# USB.net
KiCad netlist of a schematic drawn in Altium Designer
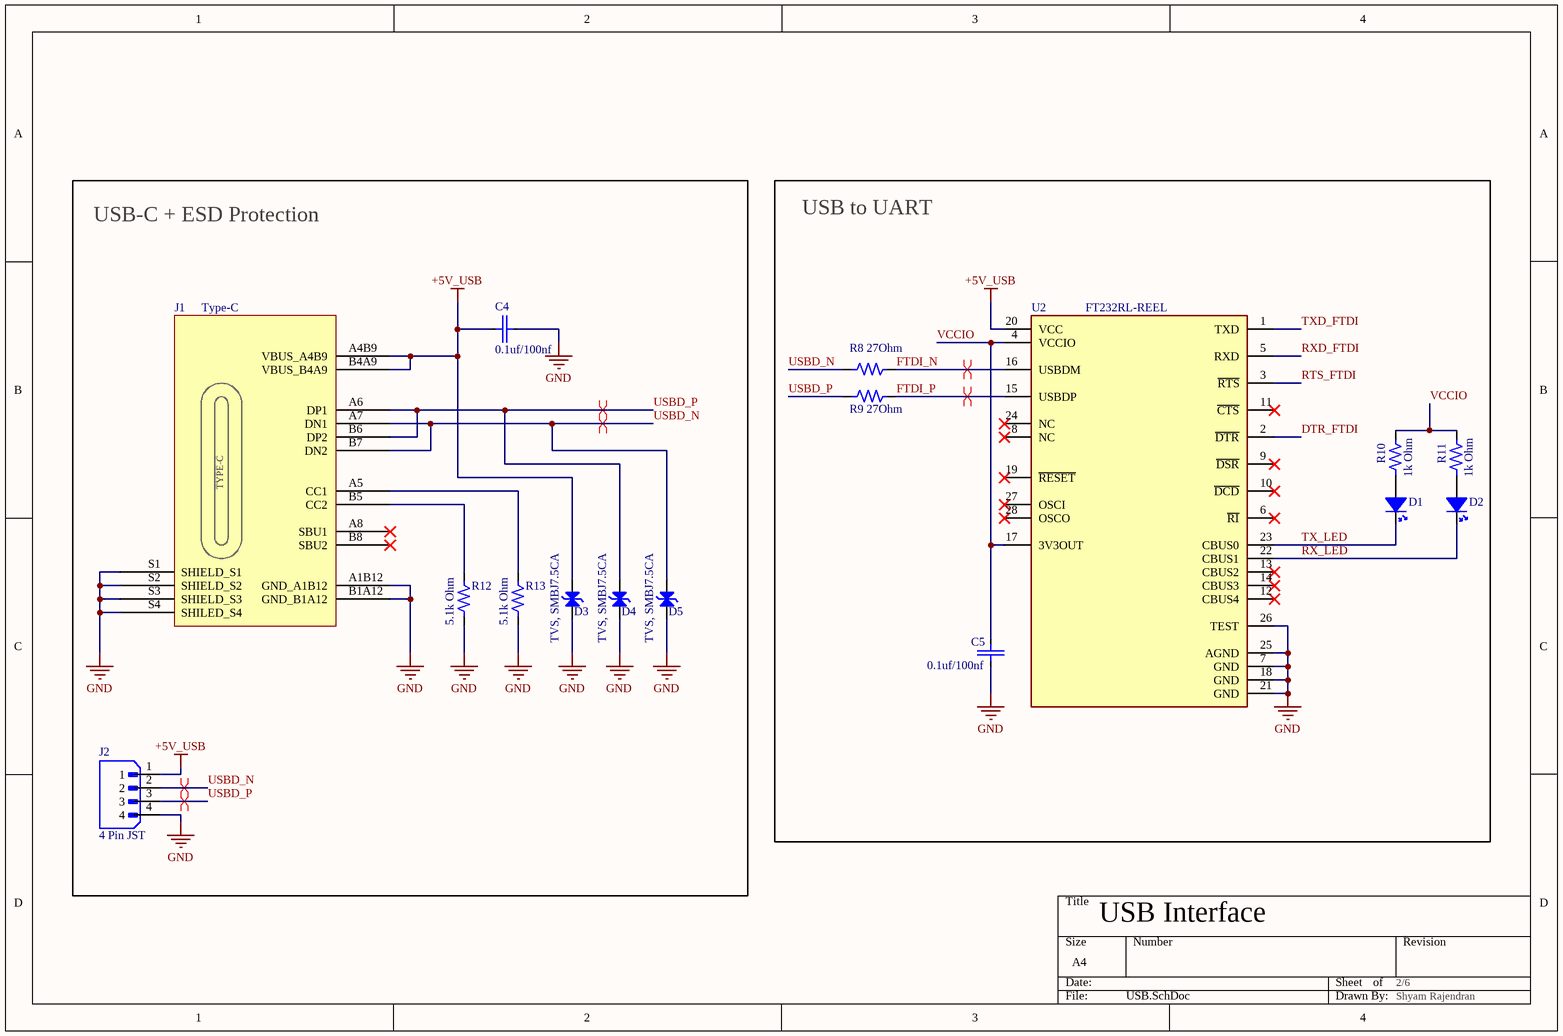
[diagram p0: USB.SchDoc]

(export (version "E")
  (design (tool "Eeschema 10.0.6"))
  (components
    (comp (ref "C4")
      (value "0.1uf/100nf")
      (footprint "0.1uF Capacitor")
      (description "0.1 uF, Multilayer Ceramic Capacitor, 50 V, ï¿½ 10%, X7R, 0805 [2012 Metric]")
      (fields
        (field (name "MANUFACTURER") "Yageo")
        (field (name "MANUFACTURER PART NUMBER") "CC0805KRX7R9BB104")
      )
      (libsource (lib "Sirius") (part "CC0805KRX7R9BB104"))
    )
    (comp (ref "C5")
      (value "0.1uf/100nf")
      (footprint "0.1uF Capacitor")
      (description "0.1 uF, Multilayer Ceramic Capacitor, 50 V, ï¿½ 10%, X7R, 0805 [2012 Metric]")
      (fields
        (field (name "MANUFACTURER") "Yageo")
        (field (name "MANUFACTURER PART NUMBER") "CC0805KRX7R9BB104")
      )
      (libsource (lib "Sirius") (part "CC0805KRX7R9BB104"))
    )
    (comp (ref "D1") (value "Blue, 0805") (footprint "led blue") (libsource (lib "Sirius") (part "LED Blue")))
    (comp (ref "D2") (value "Blue, 0805") (footprint "led blue") (libsource (lib "Sirius") (part "LED Blue")))
    (comp (ref "D3")
      (value "TVS, SMBJ7.5CA")
      (footprint "TVS Diode")
      (description "SMBJ Series 5 W 9.21 V Bi-Directional Surface Mount TVS Diode - SMB")
      (fields
        (field (name "MANUFACTURER") "Littelfuse")
        (field (name "MANUFACTURER PART NUMBER") "SMBJ7.5CA")
      )
      (libsource (lib "Sirius") (part "SMBJ7.5CA"))
    )
    (comp (ref "D4")
      (value "TVS, SMBJ7.5CA")
      (footprint "TVS Diode")
      (description "SMBJ Series 5 W 9.21 V Bi-Directional Surface Mount TVS Diode - SMB")
      (fields
        (field (name "MANUFACTURER") "Littelfuse")
        (field (name "MANUFACTURER PART NUMBER") "SMBJ7.5CA")
      )
      (libsource (lib "Sirius") (part "SMBJ7.5CA"))
    )
    (comp (ref "D5")
      (value "TVS, SMBJ7.5CA")
      (footprint "TVS Diode")
      (description "SMBJ Series 5 W 9.21 V Bi-Directional Surface Mount TVS Diode - SMB")
      (fields
        (field (name "MANUFACTURER") "Littelfuse")
        (field (name "MANUFACTURER PART NUMBER") "SMBJ7.5CA")
      )
      (libsource (lib "Sirius") (part "SMBJ7.5CA"))
    )
    (comp (ref "J1")
      (value "Type-C")
      (footprint "Type C")
      (description "USB Connector, 16 Contact(s), Female, Right Angle, Surface Mount Terminal, Locking, Receptacle")
      (fields (field (name "MANUFACTURER") "Molex") (field (name "MANUFACTURER PART NUMBER") "217179-0001"))
      (libsource (lib "Sirius") (part "Type-C"))
    )
    (comp (ref "J2")
      (value "4 Pin JST")
      (footprint "JST_B4B-XH-A")
      (description "Board Connector, 4 Contact(s), 1 Row(s), Male, Straight, Solder Terminal,")
      (fields (field (name "MANUFACTURER") "JST") (field (name "MANUFACTURER PART NUMBER") "B4B-XH-A"))
      (libsource (lib "Sirius") (part "B4B-XH-A-JST"))
    )
    (comp (ref "R8")
      (value "27Ohm")
      (footprint "1k 0805 Resistor")
      (description "27 Ohm, Res Thin Film 0805 1% 1/8W ±50ppm/°C Molded SMD SMD Paper T/R")
      (fields
        (field (name "MANUFACTURER") "Yageo")
        (field (name "MANUFACTURER PART NUMBER") "RT0805FRE0727RL")
      )
      (libsource (lib "Sirius") (part "RT0805FRE0727RL"))
    )
    (comp (ref "R9")
      (value "27Ohm")
      (footprint "1k 0805 Resistor")
      (description "27 Ohm, Res Thin Film 0805 1% 1/8W ±50ppm/°C Molded SMD SMD Paper T/R")
      (fields
        (field (name "MANUFACTURER") "Yageo")
        (field (name "MANUFACTURER PART NUMBER") "RT0805FRE0727RL")
      )
      (libsource (lib "Sirius") (part "RT0805FRE0727RL"))
    )
    (comp (ref "R10")
      (value "1k Ohm")
      (footprint "1k 0805 Resistor")
      (description "1k Ohm, 0805, SMD Chip Resistor , ï¿½ 1%, 125 mW,[2012 Metric], Thick Film, General Purpose")
      (fields
        (field (name "MANUFACTURER") "Yageo")
        (field (name "MANUFACTURER PART NUMBER") "RC0805FR-071KL")
      )
      (libsource (lib "Sirius") (part "RC0805FR-071KL"))
    )
    (comp (ref "R11")
      (value "1k Ohm")
      (footprint "1k 0805 Resistor")
      (description "1k Ohm, 0805, SMD Chip Resistor , ï¿½ 1%, 125 mW,[2012 Metric], Thick Film, General Purpose")
      (fields
        (field (name "MANUFACTURER") "Yageo")
        (field (name "MANUFACTURER PART NUMBER") "RC0805FR-071KL")
      )
      (libsource (lib "Sirius") (part "RC0805FR-071KL"))
    )
    (comp (ref "R12")
      (value "5.1k Ohm")
      (footprint "RESC2012X60N")
      (description "5.1k Ohm, 0805, 0.125W, 150V, 1% +/-Tol, 100ppm/Cel, Surface Mount")
      (fields
        (field (name "MANUFACTURER") "Yageo")
        (field (name "MANUFACTURER PART NUMBER") "RC0805FR-075K1L")
      )
      (libsource (lib "Sirius") (part "RC0805FR-075K1L"))
    )
    (comp (ref "R13")
      (value "5.1k Ohm")
      (footprint "RESC2012X60N")
      (description "5.1k Ohm, 0805, 0.125W, 150V, 1% +/-Tol, 100ppm/Cel, Surface Mount")
      (fields
        (field (name "MANUFACTURER") "Yageo")
        (field (name "MANUFACTURER PART NUMBER") "RC0805FR-075K1L")
      )
      (libsource (lib "Sirius") (part "RC0805FR-075K1L"))
    )
    (comp (ref "U2")
      (value "FT232RL-REEL")
      (footprint "FP-SSOP-28-IPC_B")
      (description "USB Bus Controller, CMOS, PDSO28")
      (fields (field (name "MANUFACTURER") "FTDI"))
      (libsource (lib "Sirius") (part "FT232RL-REEL"))
    )
  )
  (nets
    (net (code "1") (name "+5V_USB") (class "Default")
      (node (ref "C4") (pin "2") (pinfunction "2_2") (pintype "passive"))
      (node (ref "D3") (pin "2") (pinfunction "2_2") (pintype "passive"))
      (node (ref "J1") (pin "A4B9") (pinfunction "VBUS_A4B9_A4B9") (pintype "passive"))
      (node (ref "J1") (pin "B4A9") (pinfunction "VBUS_B4A9_B4A9") (pintype "passive"))
      (node (ref "J2") (pin "1") (pinfunction "1_1") (pintype "passive"))
      (node (ref "U2") (pin "20") (pinfunction "VCC_20") (pintype "passive"))
    )
    (net (code "2") (name "/DTR_FTDI") (class "Default")
      (node (ref "U2") (pin "2") (pinfunction "~{DTR}_2") (pintype "passive"))
    )
    (net (code "3") (name "/FTDI_N") (class "Default")
      (node (ref "R8") (pin "2") (pinfunction "2_2") (pintype "passive"))
      (node (ref "U2") (pin "16") (pinfunction "USBDM_16") (pintype "passive"))
    )
    (net (code "4") (name "/FTDI_P") (class "Default")
      (node (ref "R9") (pin "2") (pinfunction "2_2") (pintype "passive"))
      (node (ref "U2") (pin "15") (pinfunction "USBDP_15") (pintype "passive"))
    )
    (net (code "5") (name "/RTS_FTDI") (class "Default")
      (node (ref "U2") (pin "3") (pinfunction "~{RTS}_3") (pintype "passive"))
    )
    (net (code "6") (name "/RXD_FTDI") (class "Default")
      (node (ref "U2") (pin "5") (pinfunction "RXD_5") (pintype "passive"))
    )
    (net (code "7") (name "/RX_LED") (class "Default")
      (node (ref "D2") (pin "C") (pinfunction "2_C") (pintype "passive"))
      (node (ref "U2") (pin "22") (pinfunction "CBUS1_22") (pintype "passive"))
    )
    (net (code "8") (name "/TXD_FTDI") (class "Default")
      (node (ref "U2") (pin "1") (pinfunction "TXD_1") (pintype "passive"))
    )
    (net (code "9") (name "/TX_LED") (class "Default")
      (node (ref "D1") (pin "C") (pinfunction "2_C") (pintype "passive"))
      (node (ref "U2") (pin "23") (pinfunction "CBUS0_23") (pintype "passive"))
    )
    (net (code "10") (name "/USBD_N") (class "Default")
      (node (ref "D5") (pin "2") (pinfunction "2_2") (pintype "passive"))
      (node (ref "J1") (pin "A7") (pinfunction "DN1_A7") (pintype "passive"))
      (node (ref "J1") (pin "B7") (pinfunction "DN2_B7") (pintype "passive"))
      (node (ref "J2") (pin "2") (pinfunction "2_2") (pintype "passive"))
      (node (ref "R8") (pin "1") (pinfunction "1_1") (pintype "passive"))
    )
    (net (code "11") (name "/USBD_P") (class "Default")
      (node (ref "D4") (pin "2") (pinfunction "2_2") (pintype "passive"))
      (node (ref "J1") (pin "A6") (pinfunction "DP1_A6") (pintype "passive"))
      (node (ref "J1") (pin "B6") (pinfunction "DP2_B6") (pintype "passive"))
      (node (ref "J2") (pin "3") (pinfunction "3_3") (pintype "passive"))
      (node (ref "R9") (pin "1") (pinfunction "1_1") (pintype "passive"))
    )
    (net (code "12") (name "/VCCIO") (class "Default")
      (node (ref "C5") (pin "2") (pinfunction "2_2") (pintype "passive"))
      (node (ref "R10") (pin "2") (pinfunction "2_2") (pintype "passive"))
      (node (ref "R11") (pin "2") (pinfunction "2_2") (pintype "passive"))
      (node (ref "U2") (pin "17") (pinfunction "3V3OUT_17") (pintype "passive"))
      (node (ref "U2") (pin "4") (pinfunction "VCCIO_4") (pintype "passive"))
    )
    (net (code "13") (name "GND") (class "Default")
      (node (ref "C4") (pin "1") (pinfunction "1_1") (pintype "passive"))
      (node (ref "C5") (pin "1") (pinfunction "1_1") (pintype "passive"))
      (node (ref "D3") (pin "1") (pinfunction "1_1") (pintype "passive"))
      (node (ref "D4") (pin "1") (pinfunction "1_1") (pintype "passive"))
      (node (ref "D5") (pin "1") (pinfunction "1_1") (pintype "passive"))
      (node (ref "J1") (pin "A1B12") (pinfunction "GND_A1B12_A1B12") (pintype "passive"))
      (node (ref "J1") (pin "B1A12") (pinfunction "GND_B1A12_B1A12") (pintype "passive"))
      (node (ref "J1") (pin "S1") (pinfunction "SHIELD_S1_S1") (pintype "passive"))
      (node (ref "J1") (pin "S2") (pinfunction "SHIELD_S2_S2") (pintype "passive"))
      (node (ref "J1") (pin "S3") (pinfunction "SHIELD_S3_S3") (pintype "passive"))
      (node (ref "J1") (pin "S4") (pinfunction "SHILED_S4_S4") (pintype "passive"))
      (node (ref "J2") (pin "4") (pinfunction "4_4") (pintype "passive"))
      (node (ref "R12") (pin "1") (pinfunction "1_1") (pintype "passive"))
      (node (ref "R13") (pin "1") (pinfunction "1_1") (pintype "passive"))
      (node (ref "U2") (pin "18") (pinfunction "GND_18") (pintype "passive"))
      (node (ref "U2") (pin "21") (pinfunction "GND_21") (pintype "passive"))
      (node (ref "U2") (pin "25") (pinfunction "AGND_25") (pintype "passive"))
      (node (ref "U2") (pin "26") (pinfunction "TEST_26") (pintype "passive"))
      (node (ref "U2") (pin "7") (pinfunction "GND_7") (pintype "passive"))
    )
    (net (code "14") (name "Net-(D1-1)") (class "Default")
      (node (ref "D1") (pin "A") (pinfunction "1_A") (pintype "passive"))
      (node (ref "R10") (pin "1") (pinfunction "1_1") (pintype "passive"))
    )
    (net (code "15") (name "Net-(D2-1)") (class "Default")
      (node (ref "D2") (pin "A") (pinfunction "1_A") (pintype "passive"))
      (node (ref "R11") (pin "1") (pinfunction "1_1") (pintype "passive"))
    )
    (net (code "16") (name "Net-(J1-CC1)") (class "Default")
      (node (ref "J1") (pin "A5") (pinfunction "CC1_A5") (pintype "passive"))
      (node (ref "R13") (pin "2") (pinfunction "2_2") (pintype "passive"))
    )
    (net (code "17") (name "Net-(J1-CC2)") (class "Default")
      (node (ref "J1") (pin "B5") (pinfunction "CC2_B5") (pintype "passive"))
      (node (ref "R12") (pin "2") (pinfunction "2_2") (pintype "passive"))
    )
    (net (code "18") (name "unconnected-(J1-SBU1-PadA8)") (class "Default")
      (node (ref "J1") (pin "A8") (pinfunction "SBU1_A8") (pintype "passive+no_connect"))
    )
    (net (code "19") (name "unconnected-(J1-SBU2-PadB8)") (class "Default")
      (node (ref "J1") (pin "B8") (pinfunction "SBU2_B8") (pintype "passive+no_connect"))
    )
    (net (code "20") (name "unconnected-(U2-CBUS2-Pad13)") (class "Default")
      (node (ref "U2") (pin "13") (pinfunction "CBUS2_13") (pintype "passive+no_connect"))
    )
    (net (code "21") (name "unconnected-(U2-CBUS3-Pad14)") (class "Default")
      (node (ref "U2") (pin "14") (pinfunction "CBUS3_14") (pintype "passive+no_connect"))
    )
    (net (code "22") (name "unconnected-(U2-CBUS4-Pad12)") (class "Default")
      (node (ref "U2") (pin "12") (pinfunction "CBUS4_12") (pintype "passive+no_connect"))
    )
    (net (code "23") (name "unconnected-(U2-NC-Pad8)") (class "Default")
      (node (ref "U2") (pin "8") (pinfunction "NC_8") (pintype "passive+no_connect"))
    )
    (net (code "24") (name "unconnected-(U2-NC-Pad24)") (class "Default")
      (node (ref "U2") (pin "24") (pinfunction "NC_24") (pintype "passive+no_connect"))
    )
    (net (code "25") (name "unconnected-(U2-OSCI-Pad27)") (class "Default")
      (node (ref "U2") (pin "27") (pinfunction "OSCI_27") (pintype "passive+no_connect"))
    )
    (net (code "26") (name "unconnected-(U2-OSCO-Pad28)") (class "Default")
      (node (ref "U2") (pin "28") (pinfunction "OSCO_28") (pintype "passive+no_connect"))
    )
    (net (code "27") (name "unconnected-(U2-~{CTS}-Pad11)") (class "Default")
      (node (ref "U2") (pin "11") (pinfunction "~{CTS}_11") (pintype "passive+no_connect"))
    )
    (net (code "28") (name "unconnected-(U2-~{DCD}-Pad10)") (class "Default")
      (node (ref "U2") (pin "10") (pinfunction "~{DCD}_10") (pintype "passive+no_connect"))
    )
    (net (code "29") (name "unconnected-(U2-~{DSR}-Pad9)") (class "Default")
      (node (ref "U2") (pin "9") (pinfunction "~{DSR}_9") (pintype "passive+no_connect"))
    )
    (net (code "30") (name "unconnected-(U2-~{RESET}-Pad19)") (class "Default")
      (node (ref "U2") (pin "19") (pinfunction "~{RESET}_19") (pintype "passive+no_connect"))
    )
    (net (code "31") (name "unconnected-(U2-~{RI}-Pad6)") (class "Default")
      (node (ref "U2") (pin "6") (pinfunction "~{RI}_6") (pintype "passive+no_connect"))
    )
  )
)
